# power_supply.net
KiCad netlist of a schematic drawn in Altium Designer
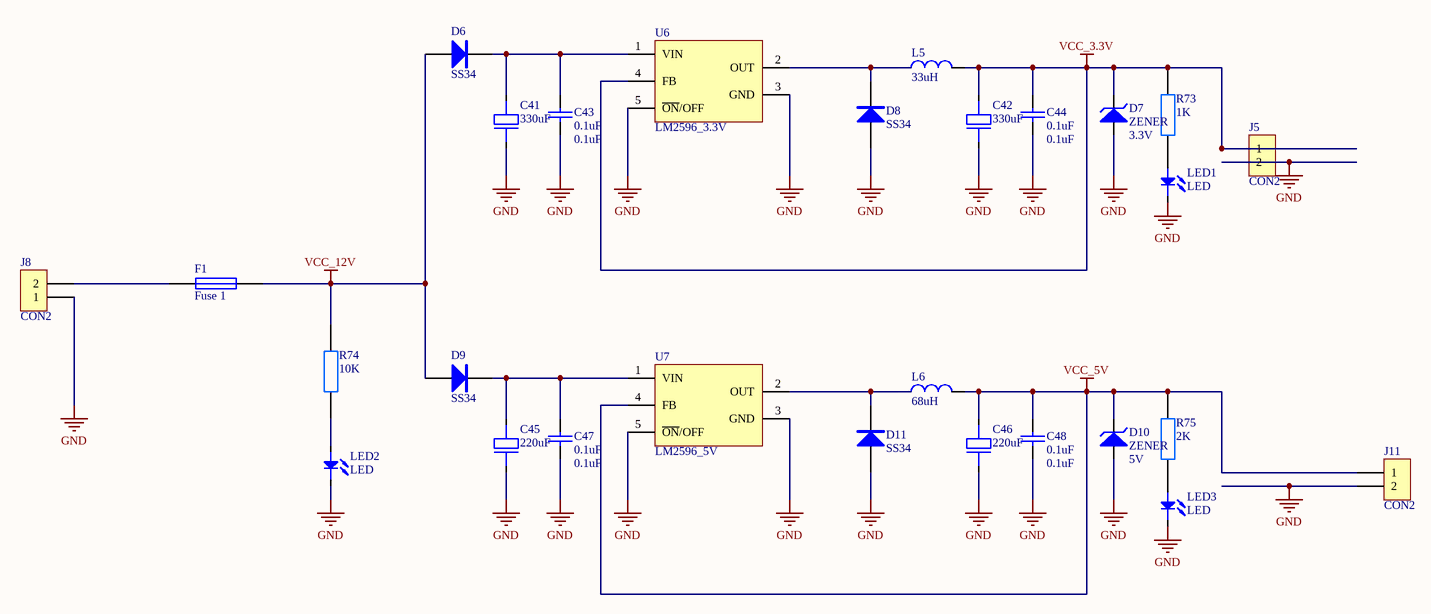
[diagram p0: power supply.SchDoc]

(export (version "E")
  (design (tool "Eeschema 10.0.6"))
  (components
    (comp (ref "C41")
      (value "330uF")
      (footprint "RVT 220uF")
      (libsource (lib "common") (part "Electrolytic CAP"))
    )
    (comp (ref "C42")
      (value "330uF")
      (footprint "RVT 220uF")
      (libsource (lib "common") (part "Electrolytic CAP"))
    )
    (comp (ref "C43")
      (value "0.1uF")
      (footprint "0805 CAP")
      (fields (field (name "ALTIUM_VALUE") "0.1uF"))
      (libsource (lib "common") (part "CAP"))
    )
    (comp (ref "C44")
      (value "0.1uF")
      (footprint "0805 CAP")
      (fields (field (name "ALTIUM_VALUE") "0.1uF"))
      (libsource (lib "common") (part "CAP"))
    )
    (comp (ref "C45")
      (value "220uF")
      (footprint "RVT 220uF")
      (libsource (lib "common") (part "Electrolytic CAP"))
    )
    (comp (ref "C46")
      (value "220uF")
      (footprint "RVT 220uF")
      (libsource (lib "common") (part "Electrolytic CAP"))
    )
    (comp (ref "C47")
      (value "0.1uF")
      (footprint "0805 CAP")
      (fields (field (name "ALTIUM_VALUE") "0.1uF"))
      (libsource (lib "common") (part "CAP"))
    )
    (comp (ref "C48")
      (value "0.1uF")
      (footprint "0805 CAP")
      (fields (field (name "ALTIUM_VALUE") "0.1uF"))
      (libsource (lib "common") (part "CAP"))
    )
    (comp (ref "D6")
      (value "SS34")
      (footprint "DO-241AC")
      (description "Diode")
      (libsource (lib "common") (part "SS14"))
    )
    (comp (ref "D7")
      (value "ZENER")
      (footprint "1206 DIODE")
      (fields (field (name "ALTIUM_VALUE") "3.3V"))
      (libsource (lib "common") (part "ZENER"))
    )
    (comp (ref "D8")
      (value "SS34")
      (footprint "DO-241AC")
      (description "Diode")
      (libsource (lib "common") (part "SS14"))
    )
    (comp (ref "D9")
      (value "SS34")
      (footprint "DO-241AC")
      (description "Diode")
      (libsource (lib "common") (part "SS14"))
    )
    (comp (ref "D10")
      (value "ZENER")
      (footprint "1206 DIODE")
      (fields (field (name "ALTIUM_VALUE") "5V"))
      (libsource (lib "common") (part "ZENER"))
    )
    (comp (ref "D11")
      (value "SS34")
      (footprint "DO-241AC")
      (description "Diode")
      (libsource (lib "common") (part "SS14"))
    )
    (comp (ref "F1")
      (value "Fuse 1")
      (footprint "FUSE1")
      (description "Fuse")
      (fields (field (name "PUBLISHER") "Altium Limited"))
      (libsource (lib "common") (part "Fuse 1"))
    )
    (comp (ref "J5") (value "CON2") (footprint "DG1282") (libsource (lib "common") (part "CON2")))
    (comp (ref "J8") (value "CON2") (footprint "con2") (libsource (lib "") (part "CON2_1")))
    (comp (ref "J11") (value "CON2") (footprint "DG1282") (libsource (lib "common") (part "CON2")))
    (comp (ref "L5") (value "33uH") (footprint "12x12") (libsource (lib "common") (part "Inductance")))
    (comp (ref "L6") (value "68uH") (footprint "12x12") (libsource (lib "common") (part "Inductance")))
    (comp (ref "LED1") (value "LED") (footprint "3528 led") (libsource (lib "common") (part "LED")))
    (comp (ref "LED2") (value "LED") (footprint "3528 LED") (libsource (lib "common") (part "LED")))
    (comp (ref "LED3") (value "LED") (footprint "3528 led") (libsource (lib "common") (part "LED")))
    (comp (ref "R73")
      (value "1K")
      (footprint "0805")
      (description "RES")
      (libsource (lib "common") (part "RES"))
    )
    (comp (ref "R74")
      (value "10K")
      (footprint "0805")
      (description "RES")
      (libsource (lib "common") (part "RES"))
    )
    (comp (ref "R75")
      (value "2K")
      (footprint "0805")
      (description "RES")
      (libsource (lib "common") (part "RES"))
    )
    (comp (ref "U6")
      (value "LM2596_3.3V")
      (footprint "to-263-5")
      (description "IC-power")
      (libsource (lib "common") (part "LM2596"))
    )
    (comp (ref "U7")
      (value "LM2596_5V")
      (footprint "to-263-5")
      (description "IC-power")
      (libsource (lib "common") (part "LM2596"))
    )
  )
  (nets
    (net (code "1") (name "GND") (class "Default")
      (node (ref "C41") (pin "2") (pinfunction "2_2") (pintype "passive"))
      (node (ref "C42") (pin "2") (pinfunction "2_2") (pintype "passive"))
      (node (ref "C43") (pin "2") (pinfunction "2_2") (pintype "passive"))
      (node (ref "C44") (pin "2") (pinfunction "2_2") (pintype "passive"))
      (node (ref "C45") (pin "2") (pinfunction "2_2") (pintype "passive"))
      (node (ref "C46") (pin "2") (pinfunction "2_2") (pintype "passive"))
      (node (ref "C47") (pin "2") (pinfunction "2_2") (pintype "passive"))
      (node (ref "C48") (pin "2") (pinfunction "2_2") (pintype "passive"))
      (node (ref "D10") (pin "1") (pinfunction "A_1") (pintype "passive"))
      (node (ref "D11") (pin "1") (pinfunction "A_1") (pintype "passive"))
      (node (ref "D7") (pin "1") (pinfunction "A_1") (pintype "passive"))
      (node (ref "D8") (pin "1") (pinfunction "A_1") (pintype "passive"))
      (node (ref "J11") (pin "2") (pinfunction "2_2") (pintype "passive"))
      (node (ref "J5") (pin "2") (pinfunction "2_2") (pintype "passive"))
      (node (ref "J8") (pin "1") (pinfunction "1_1") (pintype "passive"))
      (node (ref "LED1") (pin "2") (pintype "passive"))
      (node (ref "LED2") (pin "2") (pintype "passive"))
      (node (ref "LED3") (pin "2") (pintype "passive"))
      (node (ref "U6") (pin "3") (pinfunction "GND_3") (pintype "passive"))
      (node (ref "U6") (pin "5") (pinfunction "~{ON}/OFF_5") (pintype "passive"))
      (node (ref "U7") (pin "3") (pinfunction "GND_3") (pintype "passive"))
      (node (ref "U7") (pin "5") (pinfunction "~{ON}/OFF_5") (pintype "passive"))
    )
    (net (code "2") (name "Net-(D6-K)") (class "Default")
      (node (ref "C41") (pin "1") (pinfunction "1_1") (pintype "passive"))
      (node (ref "C43") (pin "1") (pinfunction "1_1") (pintype "passive"))
      (node (ref "D6") (pin "2") (pinfunction "K_2") (pintype "passive"))
      (node (ref "U6") (pin "1") (pinfunction "VIN_1") (pintype "passive"))
    )
    (net (code "3") (name "Net-(D8-K)") (class "Default")
      (node (ref "D8") (pin "2") (pinfunction "K_2") (pintype "passive"))
      (node (ref "L5") (pin "2") (pinfunction "2_2") (pintype "passive"))
      (node (ref "U6") (pin "2") (pinfunction "OUT_2") (pintype "passive"))
    )
    (net (code "4") (name "Net-(D9-K)") (class "Default")
      (node (ref "C45") (pin "1") (pinfunction "1_1") (pintype "passive"))
      (node (ref "C47") (pin "1") (pinfunction "1_1") (pintype "passive"))
      (node (ref "D9") (pin "2") (pinfunction "K_2") (pintype "passive"))
      (node (ref "U7") (pin "1") (pinfunction "VIN_1") (pintype "passive"))
    )
    (net (code "5") (name "Net-(D11-K)") (class "Default")
      (node (ref "D11") (pin "2") (pinfunction "K_2") (pintype "passive"))
      (node (ref "L6") (pin "2") (pinfunction "2_2") (pintype "passive"))
      (node (ref "U7") (pin "2") (pinfunction "OUT_2") (pintype "passive"))
    )
    (net (code "6") (name "Net-(F1-Pad1)") (class "Default")
      (node (ref "F1") (pin "1") (pinfunction "1_1") (pintype "passive"))
      (node (ref "J8") (pin "2") (pinfunction "2_2") (pintype "passive"))
    )
    (net (code "7") (name "Net-(LED1-Pad1)") (class "Default")
      (node (ref "LED1") (pin "1") (pintype "passive"))
      (node (ref "R73") (pin "1") (pinfunction "1_1") (pintype "passive"))
    )
    (net (code "8") (name "Net-(LED2-Pad1)") (class "Default")
      (node (ref "LED2") (pin "1") (pintype "passive"))
      (node (ref "R74") (pin "1") (pinfunction "1_1") (pintype "passive"))
    )
    (net (code "9") (name "Net-(LED3-Pad1)") (class "Default")
      (node (ref "LED3") (pin "1") (pintype "passive"))
      (node (ref "R75") (pin "1") (pinfunction "1_1") (pintype "passive"))
    )
    (net (code "10") (name "VCC_3.3V") (class "Default")
      (node (ref "C42") (pin "1") (pinfunction "1_1") (pintype "passive"))
      (node (ref "C44") (pin "1") (pinfunction "1_1") (pintype "passive"))
      (node (ref "D7") (pin "2") (pinfunction "K_2") (pintype "passive"))
      (node (ref "J5") (pin "1") (pinfunction "1_1") (pintype "passive"))
      (node (ref "L5") (pin "1") (pinfunction "1_1") (pintype "passive"))
      (node (ref "R73") (pin "2") (pinfunction "2_2") (pintype "passive"))
      (node (ref "U6") (pin "4") (pinfunction "FB_4") (pintype "passive"))
    )
    (net (code "11") (name "VCC_5V") (class "Default")
      (node (ref "C46") (pin "1") (pinfunction "1_1") (pintype "passive"))
      (node (ref "C48") (pin "1") (pinfunction "1_1") (pintype "passive"))
      (node (ref "D10") (pin "2") (pinfunction "K_2") (pintype "passive"))
      (node (ref "J11") (pin "1") (pinfunction "1_1") (pintype "passive"))
      (node (ref "L6") (pin "1") (pinfunction "1_1") (pintype "passive"))
      (node (ref "R75") (pin "2") (pinfunction "2_2") (pintype "passive"))
      (node (ref "U7") (pin "4") (pinfunction "FB_4") (pintype "passive"))
    )
    (net (code "12") (name "VCC_12V") (class "Default")
      (node (ref "D6") (pin "1") (pinfunction "A_1") (pintype "passive"))
      (node (ref "D9") (pin "1") (pinfunction "A_1") (pintype "passive"))
      (node (ref "F1") (pin "2") (pinfunction "2_2") (pintype "passive"))
      (node (ref "R74") (pin "2") (pinfunction "2_2") (pintype "passive"))
    )
  )
)
